# newbrd2.net
KiCad netlist of a schematic drawn in EAGLE
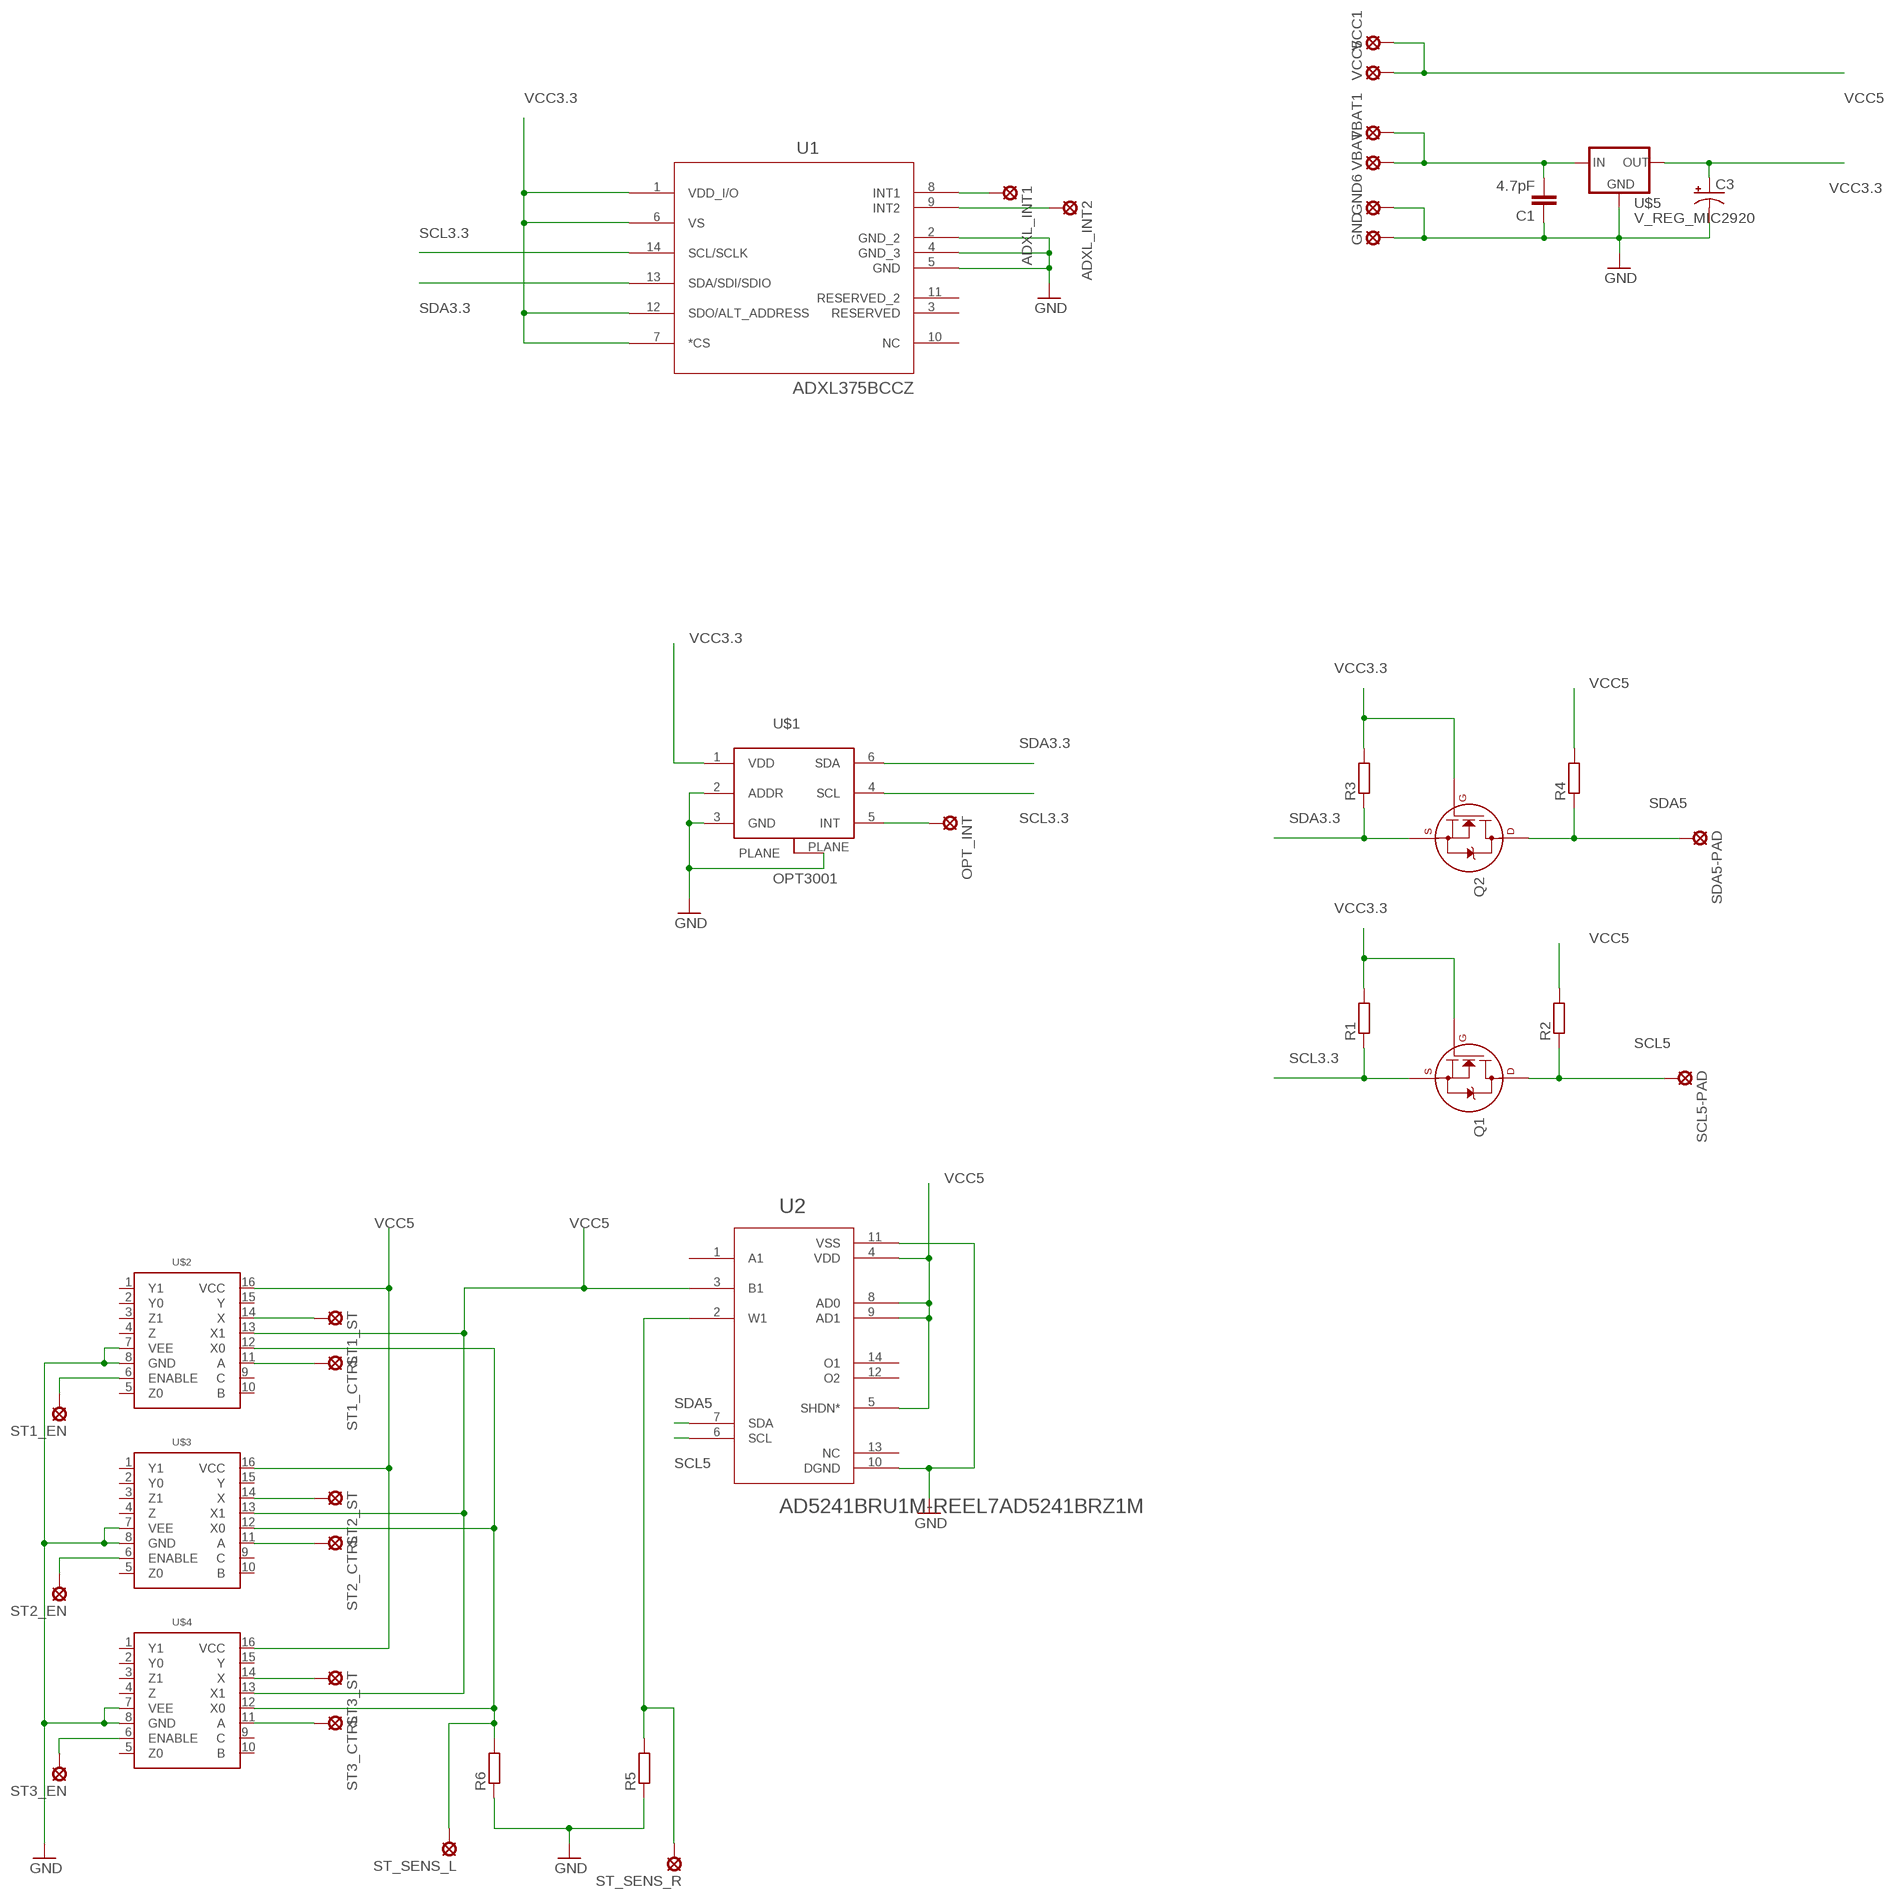
[diagram p0: schematic, sheet 1]

(export (version "E")
  (design (tool "Eeschema 10.0.6"))
  (components
    (comp (ref "ADXL_INT1")
      (value "LSP10")
      (footprint "eagle-import:LSP10")
      (libsource (lib "eagle-import") (part "LSP10"))
    )
    (comp (ref "ADXL_INT2")
      (value "LSP10")
      (footprint "eagle-import:LSP10")
      (libsource (lib "eagle-import") (part "LSP10"))
    )
    (comp (ref "C1")
      (value "4.7pF")
      (footprint "eagle-import:C0603")
      (libsource (lib "eagle-import") (part "C-EUC0603"))
    )
    (comp (ref "C3")
      (value "CAP_POL3528")
      (footprint "eagle-import:EIA3528")
      (libsource (lib "eagle-import") (part "CAP_POL3528"))
    )
    (comp (ref "GND")
      (value "LSP10")
      (footprint "eagle-import:LSP10")
      (libsource (lib "eagle-import") (part "LSP10"))
    )
    (comp (ref "GND6")
      (value "LSP10")
      (footprint "eagle-import:LSP10")
      (libsource (lib "eagle-import") (part "LSP10"))
    )
    (comp (ref "OPT_INT")
      (value "LSP10")
      (footprint "eagle-import:LSP10")
      (libsource (lib "eagle-import") (part "LSP10"))
    )
    (comp (ref "Q1")
      (value "2N7002_SOT23")
      (footprint "eagle-import:SOT-23")
      (libsource (lib "eagle-import") (part "2N700_SOT232"))
    )
    (comp (ref "Q2")
      (value "2N7002_SOT23")
      (footprint "eagle-import:SOT-23")
      (libsource (lib "eagle-import") (part "2N700_SOT232"))
    )
    (comp (ref "R1")
      (value "R-EU_R0805")
      (footprint "eagle-import:R0805")
      (libsource (lib "eagle-import") (part "R-EU_R0805"))
    )
    (comp (ref "R2")
      (value "R-EU_R0805")
      (footprint "eagle-import:R0805")
      (libsource (lib "eagle-import") (part "R-EU_R0805"))
    )
    (comp (ref "R3")
      (value "R-EU_R0805")
      (footprint "eagle-import:R0805")
      (libsource (lib "eagle-import") (part "R-EU_R0805"))
    )
    (comp (ref "R4")
      (value "R-EU_R0805")
      (footprint "eagle-import:R0805")
      (libsource (lib "eagle-import") (part "R-EU_R0805"))
    )
    (comp (ref "R5")
      (value "R-EU_R0805")
      (footprint "eagle-import:R0805")
      (libsource (lib "eagle-import") (part "R-EU_R0805"))
    )
    (comp (ref "R6")
      (value "R-EU_R0805")
      (footprint "eagle-import:R0805")
      (libsource (lib "eagle-import") (part "R-EU_R0805"))
    )
    (comp (ref "SCL5-PAD")
      (value "LSP10")
      (footprint "eagle-import:LSP10")
      (libsource (lib "eagle-import") (part "LSP10"))
    )
    (comp (ref "SDA5-PAD")
      (value "LSP10")
      (footprint "eagle-import:LSP10")
      (libsource (lib "eagle-import") (part "LSP10"))
    )
    (comp (ref "ST1_CTRL")
      (value "LSP10")
      (footprint "eagle-import:LSP10")
      (libsource (lib "eagle-import") (part "LSP10"))
    )
    (comp (ref "ST1_EN")
      (value "LSP10")
      (footprint "eagle-import:LSP10")
      (libsource (lib "eagle-import") (part "LSP10"))
    )
    (comp (ref "ST1_ST")
      (value "LSP10")
      (footprint "eagle-import:LSP10")
      (libsource (lib "eagle-import") (part "LSP10"))
    )
    (comp (ref "ST2_CTRL")
      (value "LSP10")
      (footprint "eagle-import:LSP10")
      (libsource (lib "eagle-import") (part "LSP10"))
    )
    (comp (ref "ST2_EN")
      (value "LSP10")
      (footprint "eagle-import:LSP10")
      (libsource (lib "eagle-import") (part "LSP10"))
    )
    (comp (ref "ST2_ST")
      (value "LSP10")
      (footprint "eagle-import:LSP10")
      (libsource (lib "eagle-import") (part "LSP10"))
    )
    (comp (ref "ST3_CTRL")
      (value "LSP10")
      (footprint "eagle-import:LSP10")
      (libsource (lib "eagle-import") (part "LSP10"))
    )
    (comp (ref "ST3_EN")
      (value "LSP10")
      (footprint "eagle-import:LSP10")
      (libsource (lib "eagle-import") (part "LSP10"))
    )
    (comp (ref "ST3_ST")
      (value "LSP10")
      (footprint "eagle-import:LSP10")
      (libsource (lib "eagle-import") (part "LSP10"))
    )
    (comp (ref "ST_SENS_L")
      (value "LSP10")
      (footprint "eagle-import:LSP10")
      (libsource (lib "eagle-import") (part "LSP10"))
    )
    (comp (ref "ST_SENS_R")
      (value "LSP10")
      (footprint "eagle-import:LSP10")
      (libsource (lib "eagle-import") (part "LSP10"))
    )
    (comp (ref "U$1")
      (value "OPT3001")
      (footprint "eagle-import:OPT3001")
      (libsource (lib "eagle-import") (part "OPT3001"))
    )
    (comp (ref "U$2")
      (value "MC74HC4051AMC74HC4051AG")
      (footprint "eagle-import:SOIC-16")
      (libsource (lib "eagle-import") (part "MC74HC4051AMC74HC4051AG"))
    )
    (comp (ref "U$3")
      (value "MC74HC4051AMC74HC4051AG")
      (footprint "eagle-import:SOIC-16")
      (libsource (lib "eagle-import") (part "MC74HC4051AMC74HC4051AG"))
    )
    (comp (ref "U$4")
      (value "MC74HC4051AMC74HC4051AG")
      (footprint "eagle-import:SOIC-16")
      (libsource (lib "eagle-import") (part "MC74HC4051AMC74HC4051AG"))
    )
    (comp (ref "U$5")
      (value "V_REG_MIC2920")
      (footprint "eagle-import:SOT223")
      (libsource (lib "eagle-import") (part "V_REG_MIC2920"))
    )
    (comp (ref "U1")
      (value "ADXL375BCCZ")
      (footprint "eagle-import:LGA_CC-14-1")
      (libsource (lib "eagle-import") (part "ADXL375BCCZ"))
    )
    (comp (ref "U2")
      (value "AD5241BRU1M-REEL7AD5241BRZ1M")
      (footprint "eagle-import:SOIC-14")
      (libsource (lib "eagle-import") (part "AD5241BRU1M-REEL7AD5241BRZ1M"))
    )
    (comp (ref "VBAT")
      (value "LSP10")
      (footprint "eagle-import:LSP10")
      (libsource (lib "eagle-import") (part "LSP10"))
    )
    (comp (ref "VBAT1")
      (value "LSP10")
      (footprint "eagle-import:LSP10")
      (libsource (lib "eagle-import") (part "LSP10"))
    )
    (comp (ref "VCC1")
      (value "LSP10")
      (footprint "eagle-import:LSP10")
      (libsource (lib "eagle-import") (part "LSP10"))
    )
    (comp (ref "VCC5")
      (value "LSP10")
      (footprint "eagle-import:LSP10")
      (libsource (lib "eagle-import") (part "LSP10"))
    )
  )
  (nets
    (net (code "1") (name "/SCL3.3") (class "Default")
      (node (ref "Q1") (pin "2") (pinfunction "S_2") (pintype "bidirectional"))
      (node (ref "R1") (pin "1") (pinfunction "1_1") (pintype "passive"))
      (node (ref "U$1") (pin "4") (pinfunction "SCL_4") (pintype "bidirectional"))
      (node (ref "U1") (pin "14") (pinfunction "SCL/SCLK_14") (pintype "passive"))
    )
    (net (code "2") (name "/SCL5") (class "Default")
      (node (ref "Q1") (pin "3") (pinfunction "D_3") (pintype "bidirectional"))
      (node (ref "R2") (pin "1") (pinfunction "1_1") (pintype "passive"))
      (node (ref "SCL5-PAD") (pin "MP") (pinfunction "MP_MP") (pintype "passive"))
      (node (ref "U2") (pin "6") (pinfunction "SCL_6") (pintype "passive"))
    )
    (net (code "3") (name "/SDA3.3") (class "Default")
      (node (ref "Q2") (pin "2") (pinfunction "S_2") (pintype "bidirectional"))
      (node (ref "R3") (pin "1") (pinfunction "1_1") (pintype "passive"))
      (node (ref "U$1") (pin "6") (pinfunction "SDA_6") (pintype "bidirectional"))
      (node (ref "U1") (pin "13") (pinfunction "SDA/SDI/SDIO_13") (pintype "passive"))
    )
    (net (code "4") (name "/SDA5") (class "Default")
      (node (ref "Q2") (pin "3") (pinfunction "D_3") (pintype "bidirectional"))
      (node (ref "R4") (pin "1") (pinfunction "1_1") (pintype "passive"))
      (node (ref "SDA5-PAD") (pin "MP") (pinfunction "MP_MP") (pintype "passive"))
      (node (ref "U2") (pin "7") (pinfunction "SDA_7") (pintype "passive"))
    )
    (net (code "5") (name "/VCC3.3") (class "Default")
      (node (ref "C3") (pin "A") (pinfunction "+_A") (pintype "passive"))
      (node (ref "Q1") (pin "1") (pinfunction "G_1") (pintype "tri_state"))
      (node (ref "Q2") (pin "1") (pinfunction "G_1") (pintype "tri_state"))
      (node (ref "R1") (pin "2") (pinfunction "2_2") (pintype "passive"))
      (node (ref "R3") (pin "2") (pinfunction "2_2") (pintype "passive"))
      (node (ref "U$1") (pin "1") (pinfunction "VDD_1") (pintype "power_in"))
      (node (ref "U$5") (pin "3") (pinfunction "OUT_3") (pintype "passive"))
      (node (ref "U1") (pin "1") (pinfunction "VDD_I/O_1") (pintype "passive"))
      (node (ref "U1") (pin "12") (pinfunction "SDO/ALT_ADDRESS_12") (pintype "passive"))
      (node (ref "U1") (pin "6") (pinfunction "VS_6") (pintype "passive"))
      (node (ref "U1") (pin "7") (pinfunction "*CS_7") (pintype "passive"))
    )
    (net (code "6") (name "/VCC5") (class "Default")
      (node (ref "R2") (pin "2") (pinfunction "2_2") (pintype "passive"))
      (node (ref "R4") (pin "2") (pinfunction "2_2") (pintype "passive"))
      (node (ref "U$2") (pin "13") (pinfunction "X1_13") (pintype "bidirectional"))
      (node (ref "U$2") (pin "16") (pinfunction "VCC_16") (pintype "bidirectional"))
      (node (ref "U$3") (pin "13") (pinfunction "X1_13") (pintype "bidirectional"))
      (node (ref "U$3") (pin "16") (pinfunction "VCC_16") (pintype "bidirectional"))
      (node (ref "U$4") (pin "13") (pinfunction "X1_13") (pintype "bidirectional"))
      (node (ref "U$4") (pin "16") (pinfunction "VCC_16") (pintype "bidirectional"))
      (node (ref "U2") (pin "3") (pinfunction "B1_3") (pintype "passive"))
      (node (ref "U2") (pin "4") (pinfunction "VDD_4") (pintype "power_in"))
      (node (ref "U2") (pin "5") (pinfunction "SHDN*_5") (pintype "passive"))
      (node (ref "U2") (pin "8") (pinfunction "AD0_8") (pintype "passive"))
      (node (ref "U2") (pin "9") (pinfunction "AD1_9") (pintype "passive"))
      (node (ref "VCC1") (pin "MP") (pinfunction "MP_MP") (pintype "passive"))
      (node (ref "VCC5") (pin "MP") (pinfunction "MP_MP") (pintype "passive"))
    )
    (net (code "7") (name "GND") (class "Default")
      (node (ref "C1") (pin "1") (pinfunction "1_1") (pintype "passive"))
      (node (ref "C3") (pin "C") (pinfunction "-_C") (pintype "passive"))
      (node (ref "GND") (pin "MP") (pinfunction "MP_MP") (pintype "passive"))
      (node (ref "GND6") (pin "MP") (pinfunction "MP_MP") (pintype "passive"))
      (node (ref "R5") (pin "1") (pinfunction "1_1") (pintype "passive"))
      (node (ref "R6") (pin "1") (pinfunction "1_1") (pintype "passive"))
      (node (ref "U$1") (pin "2") (pinfunction "ADDR_2") (pintype "bidirectional"))
      (node (ref "U$1") (pin "3") (pinfunction "GND_3") (pintype "power_in"))
      (node (ref "U$1") (pin "PLANE") (pinfunction "PLANE_PLANE") (pintype "bidirectional"))
      (node (ref "U$2") (pin "7") (pinfunction "VEE_7") (pintype "bidirectional"))
      (node (ref "U$2") (pin "8") (pinfunction "GND_8") (pintype "bidirectional"))
      (node (ref "U$3") (pin "7") (pinfunction "VEE_7") (pintype "bidirectional"))
      (node (ref "U$3") (pin "8") (pinfunction "GND_8") (pintype "bidirectional"))
      (node (ref "U$4") (pin "7") (pinfunction "VEE_7") (pintype "bidirectional"))
      (node (ref "U$4") (pin "8") (pinfunction "GND_8") (pintype "bidirectional"))
      (node (ref "U$5") (pin "2") (pinfunction "GND_2") (pintype "input"))
      (node (ref "U1") (pin "2") (pinfunction "GND_2_2") (pintype "passive"))
      (node (ref "U1") (pin "4") (pinfunction "GND_3_4") (pintype "passive"))
      (node (ref "U1") (pin "5") (pinfunction "GND_5") (pintype "passive"))
      (node (ref "U2") (pin "10") (pinfunction "DGND_10") (pintype "passive"))
      (node (ref "U2") (pin "11") (pinfunction "VSS_11") (pintype "power_in"))
    )
    (net (code "8") (name "Net-(U$1-INT)") (class "Default")
      (node (ref "OPT_INT") (pin "MP") (pinfunction "MP_MP") (pintype "passive"))
      (node (ref "U$1") (pin "5") (pinfunction "INT_5") (pintype "output"))
    )
    (net (code "9") (name "Net-(U$2-A)") (class "Default")
      (node (ref "ST1_CTRL") (pin "MP") (pinfunction "MP_MP") (pintype "passive"))
      (node (ref "U$2") (pin "11") (pinfunction "A_11") (pintype "bidirectional"))
    )
    (net (code "10") (name "Net-(U$2-ENABLE)") (class "Default")
      (node (ref "ST1_EN") (pin "MP") (pinfunction "MP_MP") (pintype "passive"))
      (node (ref "U$2") (pin "6") (pinfunction "ENABLE_6") (pintype "bidirectional"))
    )
    (net (code "11") (name "Net-(U$2-X)") (class "Default")
      (node (ref "ST1_ST") (pin "MP") (pinfunction "MP_MP") (pintype "passive"))
      (node (ref "U$2") (pin "14") (pinfunction "X_14") (pintype "bidirectional"))
    )
    (net (code "12") (name "Net-(U$2-X0)") (class "Default")
      (node (ref "R6") (pin "2") (pinfunction "2_2") (pintype "passive"))
      (node (ref "ST_SENS_L") (pin "MP") (pinfunction "MP_MP") (pintype "passive"))
      (node (ref "U$2") (pin "12") (pinfunction "X0_12") (pintype "bidirectional"))
      (node (ref "U$3") (pin "12") (pinfunction "X0_12") (pintype "bidirectional"))
      (node (ref "U$4") (pin "12") (pinfunction "X0_12") (pintype "bidirectional"))
    )
    (net (code "13") (name "Net-(U$3-A)") (class "Default")
      (node (ref "ST2_CTRL") (pin "MP") (pinfunction "MP_MP") (pintype "passive"))
      (node (ref "U$3") (pin "11") (pinfunction "A_11") (pintype "bidirectional"))
    )
    (net (code "14") (name "Net-(U$3-ENABLE)") (class "Default")
      (node (ref "ST2_EN") (pin "MP") (pinfunction "MP_MP") (pintype "passive"))
      (node (ref "U$3") (pin "6") (pinfunction "ENABLE_6") (pintype "bidirectional"))
    )
    (net (code "15") (name "Net-(U$3-X)") (class "Default")
      (node (ref "ST2_ST") (pin "MP") (pinfunction "MP_MP") (pintype "passive"))
      (node (ref "U$3") (pin "14") (pinfunction "X_14") (pintype "bidirectional"))
    )
    (net (code "16") (name "Net-(U$4-A)") (class "Default")
      (node (ref "ST3_CTRL") (pin "MP") (pinfunction "MP_MP") (pintype "passive"))
      (node (ref "U$4") (pin "11") (pinfunction "A_11") (pintype "bidirectional"))
    )
    (net (code "17") (name "Net-(U$4-ENABLE)") (class "Default")
      (node (ref "ST3_EN") (pin "MP") (pinfunction "MP_MP") (pintype "passive"))
      (node (ref "U$4") (pin "6") (pinfunction "ENABLE_6") (pintype "bidirectional"))
    )
    (net (code "18") (name "Net-(U$4-X)") (class "Default")
      (node (ref "ST3_ST") (pin "MP") (pinfunction "MP_MP") (pintype "passive"))
      (node (ref "U$4") (pin "14") (pinfunction "X_14") (pintype "bidirectional"))
    )
    (net (code "19") (name "Net-(U$5-IN)") (class "Default")
      (node (ref "C1") (pin "2") (pinfunction "2_2") (pintype "passive"))
      (node (ref "U$5") (pin "1") (pinfunction "IN_1") (pintype "input"))
      (node (ref "VBAT") (pin "MP") (pinfunction "MP_MP") (pintype "passive"))
      (node (ref "VBAT1") (pin "MP") (pinfunction "MP_MP") (pintype "passive"))
    )
    (net (code "20") (name "Net-(U1-INT1)") (class "Default")
      (node (ref "ADXL_INT1") (pin "MP") (pinfunction "MP_MP") (pintype "passive"))
      (node (ref "U1") (pin "8") (pinfunction "INT1_8") (pintype "passive"))
    )
    (net (code "21") (name "Net-(U1-INT2)") (class "Default")
      (node (ref "ADXL_INT2") (pin "MP") (pinfunction "MP_MP") (pintype "passive"))
      (node (ref "U1") (pin "9") (pinfunction "INT2_9") (pintype "passive"))
    )
    (net (code "22") (name "Net-(U2-W1)") (class "Default")
      (node (ref "R5") (pin "2") (pinfunction "2_2") (pintype "passive"))
      (node (ref "ST_SENS_R") (pin "MP") (pinfunction "MP_MP") (pintype "passive"))
      (node (ref "U2") (pin "2") (pinfunction "W1_2") (pintype "passive"))
    )
    (net (code "23") (name "unconnected-(U$2-B-Pad10)") (class "Default")
      (node (ref "U$2") (pin "10") (pinfunction "B_10") (pintype "bidirectional"))
    )
    (net (code "24") (name "unconnected-(U$2-C-Pad9)") (class "Default")
      (node (ref "U$2") (pin "9") (pinfunction "C_9") (pintype "bidirectional"))
    )
    (net (code "25") (name "unconnected-(U$2-Y-Pad15)") (class "Default")
      (node (ref "U$2") (pin "15") (pinfunction "Y_15") (pintype "bidirectional"))
    )
    (net (code "26") (name "unconnected-(U$2-Y0-Pad2)") (class "Default")
      (node (ref "U$2") (pin "2") (pinfunction "Y0_2") (pintype "bidirectional"))
    )
    (net (code "27") (name "unconnected-(U$2-Y1-Pad1)") (class "Default")
      (node (ref "U$2") (pin "1") (pinfunction "Y1_1") (pintype "bidirectional"))
    )
    (net (code "28") (name "unconnected-(U$2-Z-Pad4)") (class "Default")
      (node (ref "U$2") (pin "4") (pinfunction "Z_4") (pintype "bidirectional"))
    )
    (net (code "29") (name "unconnected-(U$2-Z0-Pad5)") (class "Default")
      (node (ref "U$2") (pin "5") (pinfunction "Z0_5") (pintype "bidirectional"))
    )
    (net (code "30") (name "unconnected-(U$2-Z1-Pad3)") (class "Default")
      (node (ref "U$2") (pin "3") (pinfunction "Z1_3") (pintype "bidirectional"))
    )
    (net (code "31") (name "unconnected-(U$3-B-Pad10)") (class "Default")
      (node (ref "U$3") (pin "10") (pinfunction "B_10") (pintype "bidirectional"))
    )
    (net (code "32") (name "unconnected-(U$3-C-Pad9)") (class "Default")
      (node (ref "U$3") (pin "9") (pinfunction "C_9") (pintype "bidirectional"))
    )
    (net (code "33") (name "unconnected-(U$3-Y-Pad15)") (class "Default")
      (node (ref "U$3") (pin "15") (pinfunction "Y_15") (pintype "bidirectional"))
    )
    (net (code "34") (name "unconnected-(U$3-Y0-Pad2)") (class "Default")
      (node (ref "U$3") (pin "2") (pinfunction "Y0_2") (pintype "bidirectional"))
    )
    (net (code "35") (name "unconnected-(U$3-Y1-Pad1)") (class "Default")
      (node (ref "U$3") (pin "1") (pinfunction "Y1_1") (pintype "bidirectional"))
    )
    (net (code "36") (name "unconnected-(U$3-Z-Pad4)") (class "Default")
      (node (ref "U$3") (pin "4") (pinfunction "Z_4") (pintype "bidirectional"))
    )
    (net (code "37") (name "unconnected-(U$3-Z0-Pad5)") (class "Default")
      (node (ref "U$3") (pin "5") (pinfunction "Z0_5") (pintype "bidirectional"))
    )
    (net (code "38") (name "unconnected-(U$3-Z1-Pad3)") (class "Default")
      (node (ref "U$3") (pin "3") (pinfunction "Z1_3") (pintype "bidirectional"))
    )
    (net (code "39") (name "unconnected-(U$4-B-Pad10)") (class "Default")
      (node (ref "U$4") (pin "10") (pinfunction "B_10") (pintype "bidirectional"))
    )
    (net (code "40") (name "unconnected-(U$4-C-Pad9)") (class "Default")
      (node (ref "U$4") (pin "9") (pinfunction "C_9") (pintype "bidirectional"))
    )
    (net (code "41") (name "unconnected-(U$4-Y-Pad15)") (class "Default")
      (node (ref "U$4") (pin "15") (pinfunction "Y_15") (pintype "bidirectional"))
    )
    (net (code "42") (name "unconnected-(U$4-Y0-Pad2)") (class "Default")
      (node (ref "U$4") (pin "2") (pinfunction "Y0_2") (pintype "bidirectional"))
    )
    (net (code "43") (name "unconnected-(U$4-Y1-Pad1)") (class "Default")
      (node (ref "U$4") (pin "1") (pinfunction "Y1_1") (pintype "bidirectional"))
    )
    (net (code "44") (name "unconnected-(U$4-Z-Pad4)") (class "Default")
      (node (ref "U$4") (pin "4") (pinfunction "Z_4") (pintype "bidirectional"))
    )
    (net (code "45") (name "unconnected-(U$4-Z0-Pad5)") (class "Default")
      (node (ref "U$4") (pin "5") (pinfunction "Z0_5") (pintype "bidirectional"))
    )
    (net (code "46") (name "unconnected-(U$4-Z1-Pad3)") (class "Default")
      (node (ref "U$4") (pin "3") (pinfunction "Z1_3") (pintype "bidirectional"))
    )
    (net (code "47") (name "unconnected-(U1-NC-Pad10)") (class "Default")
      (node (ref "U1") (pin "10") (pinfunction "NC_10") (pintype "passive"))
    )
    (net (code "48") (name "unconnected-(U1-RESERVED-Pad3)") (class "Default")
      (node (ref "U1") (pin "3") (pinfunction "RESERVED_3") (pintype "passive"))
    )
    (net (code "49") (name "unconnected-(U1-RESERVED_2-Pad11)") (class "Default")
      (node (ref "U1") (pin "11") (pinfunction "RESERVED_2_11") (pintype "passive"))
    )
    (net (code "50") (name "unconnected-(U2-A1-Pad1)") (class "Default")
      (node (ref "U2") (pin "1") (pinfunction "A1_1") (pintype "passive"))
    )
    (net (code "51") (name "unconnected-(U2-NC-Pad13)") (class "Default")
      (node (ref "U2") (pin "13") (pinfunction "NC_13") (pintype "passive"))
    )
    (net (code "52") (name "unconnected-(U2-O1-Pad14)") (class "Default")
      (node (ref "U2") (pin "14") (pinfunction "O1_14") (pintype "passive"))
    )
    (net (code "53") (name "unconnected-(U2-O2-Pad12)") (class "Default")
      (node (ref "U2") (pin "12") (pinfunction "O2_12") (pintype "passive"))
    )
  )
)
